# design.net
KiCad netlist of a schematic drawn in EasyEDA Pro
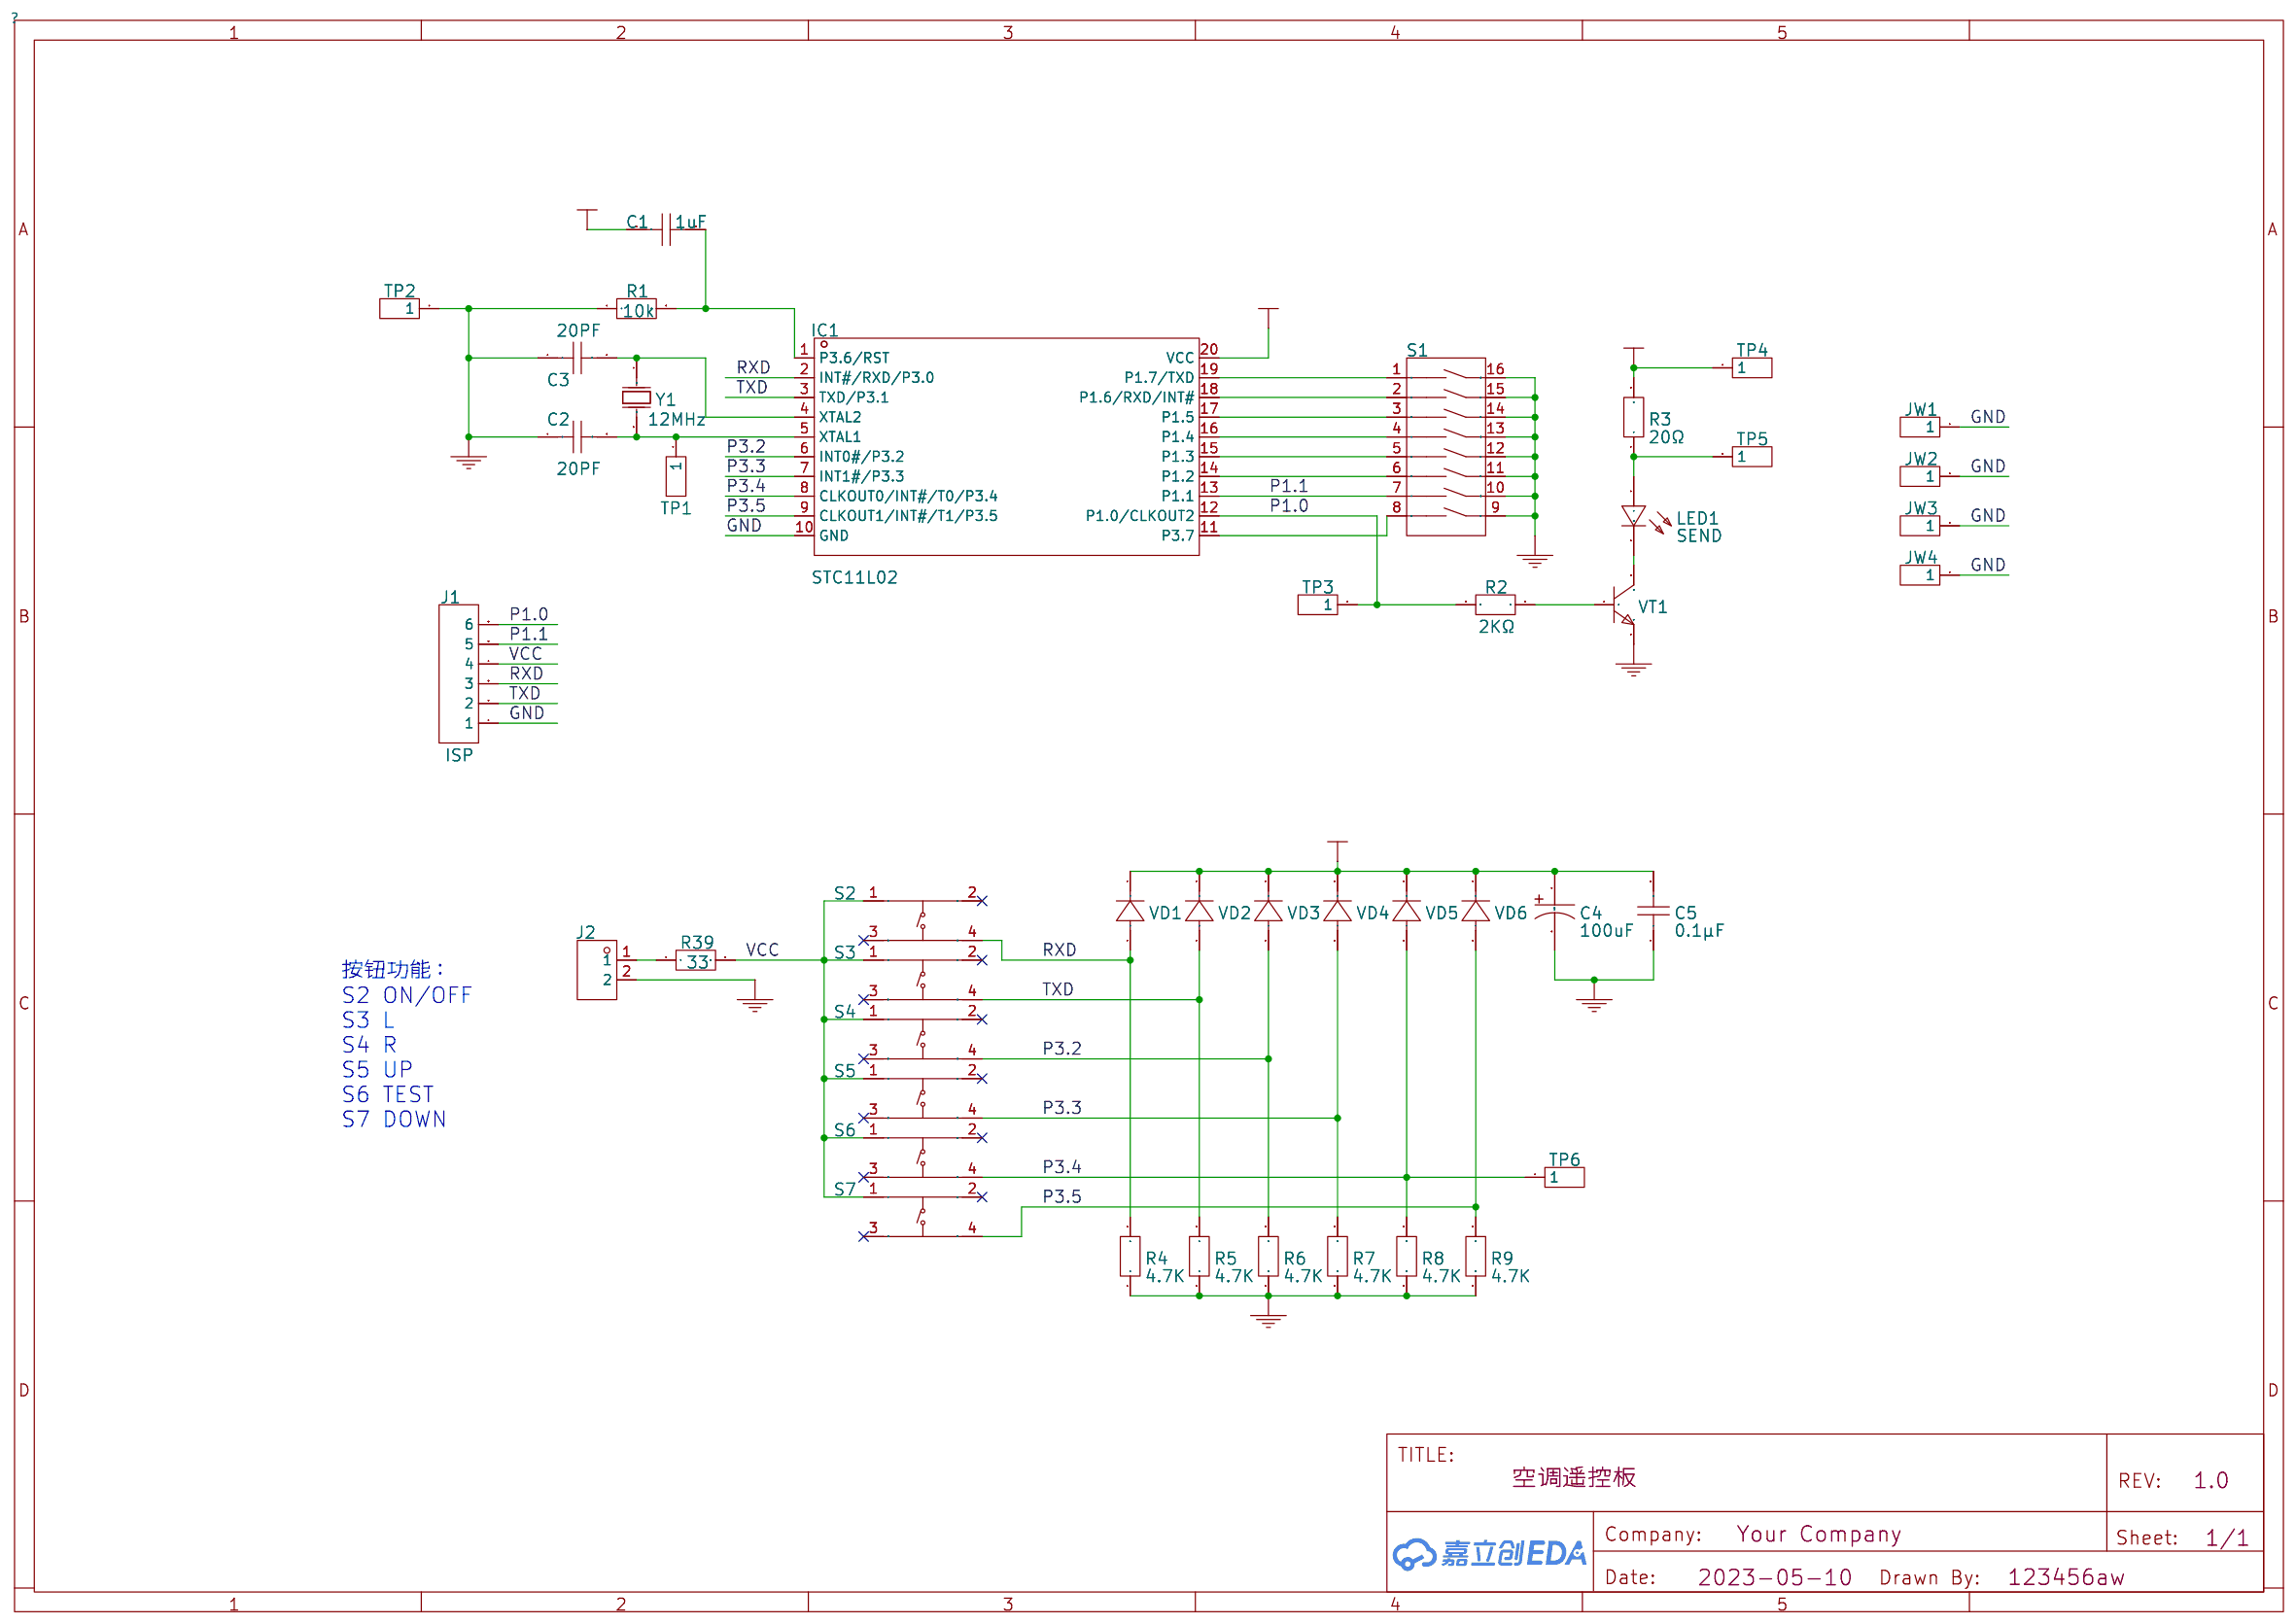
[diagram p0: schematic sheet]

(export (version "E")
  (design (tool "Eeschema 10.0.6"))
  (components
    (comp (ref "C1") (value "1uF") (footprint "easyedapro:C0805") (libsource (lib "easyedapro") (part "1uF")))
    (comp (ref "C2")
      (value "20PF")
      (footprint "easyedapro:C0805")
      (libsource (lib "easyedapro") (part "20PF"))
    )
    (comp (ref "C3")
      (value "20PF")
      (footprint "easyedapro:C0805")
      (libsource (lib "easyedapro") (part "20PF"))
    )
    (comp (ref "C4")
      (value "100uF")
      (footprint "easyedapro:CASE-C_6032")
      (fields (field (name "Manufacturer Part") "F931C107KCC") (field (name "Manufacturer") "Kyocera AVX"))
      (libsource (lib "easyedapro") (part "100uF"))
    )
    (comp (ref "C5")
      (value "0.1μF")
      (footprint "easyedapro:C0805")
      (libsource (lib "easyedapro") (part "0.1μF"))
    )
    (comp (ref "IC1")
      (value "STC11L02")
      (footprint "easyedapro:SOIC-20_L13.0-W7.6-P1.27-LS10.3-BL")
      (fields (field (name "Manufacturer") "STC(宏晶)"))
      (libsource (lib "easyedapro") (part "STC11L02"))
    )
    (comp (ref "J1")
      (value "ISP")
      (footprint "easyedapro:HDR-F-2.54_1X6")
      (libsource (lib "easyedapro") (part "ISP"))
    )
    (comp (ref "J2")
      (value "+3V GND")
      (footprint "easyedapro:CONN-TH_HX20020-2A")
      (fields (field (name "Manufacturer Part") "HX20020-2A") (field (name "Manufacturer") "HX(红星)"))
      (libsource (lib "easyedapro") (part "+3V GND"))
    )
    (comp (ref "JW1")
      (value "HDR-M-2.54_1x1")
      (footprint "easyedapro:焊盘M3")
      (libsource (lib "easyedapro") (part "HDR-M-2.54_1x1"))
    )
    (comp (ref "JW2")
      (value "HDR-M-2.54_1x1")
      (footprint "easyedapro:焊盘M3")
      (libsource (lib "easyedapro") (part "HDR-M-2.54_1x1"))
    )
    (comp (ref "JW3")
      (value "HDR-M-2.54_1x1")
      (footprint "easyedapro:焊盘M3")
      (libsource (lib "easyedapro") (part "HDR-M-2.54_1x1"))
    )
    (comp (ref "JW4")
      (value "HDR-M-2.54_1x1")
      (footprint "easyedapro:焊盘M3")
      (libsource (lib "easyedapro") (part "HDR-M-2.54_1x1"))
    )
    (comp (ref "LED1")
      (value "SEND")
      (footprint "easyedapro:LED-TH_BD3.9-P2.54-FD")
      (fields (field (name "Manufacturer Part") "IR204C-A-L") (field (name "Manufacturer") "EVERLIGHT(亿光)"))
      (libsource (lib "") (part "SEND_1"))
    )
    (comp (ref "R1") (value "10k") (footprint "easyedapro:R0805") (libsource (lib "easyedapro") (part "10k")))
    (comp (ref "R2") (value "2KΩ") (footprint "easyedapro:R0805") (libsource (lib "easyedapro") (part "2KΩ")))
    (comp (ref "R3")
      (value "20Ω")
      (footprint "easyedapro:RES-TH_BD3.5-L9.0-P13.00-D0.5")
      (fields (field (name "Manufacturer Part") "KNP1/2W-51Ω±5%-XT52") (field (name "Manufacturer") "VO(翔胜)"))
      (libsource (lib "easyedapro") (part "20Ω"))
    )
    (comp (ref "R4")
      (value "4.7K")
      (footprint "easyedapro:R0805")
      (libsource (lib "easyedapro") (part "4.7K"))
    )
    (comp (ref "R5")
      (value "4.7K")
      (footprint "easyedapro:R0805")
      (libsource (lib "easyedapro") (part "4.7K"))
    )
    (comp (ref "R6")
      (value "4.7K")
      (footprint "easyedapro:R0805")
      (libsource (lib "easyedapro") (part "4.7K"))
    )
    (comp (ref "R7")
      (value "4.7K")
      (footprint "easyedapro:R0805")
      (libsource (lib "easyedapro") (part "4.7K"))
    )
    (comp (ref "R8")
      (value "4.7K")
      (footprint "easyedapro:R0805")
      (libsource (lib "easyedapro") (part "4.7K"))
    )
    (comp (ref "R9")
      (value "4.7K")
      (footprint "easyedapro:R0805")
      (libsource (lib "easyedapro") (part "4.7K"))
    )
    (comp (ref "R39") (value "33") (footprint "easyedapro:R0805") (libsource (lib "easyedapro") (part "33")))
    (comp (ref "S1")
      (value "ADD")
      (footprint "easyedapro:SW-TH_16P-L21.9-W9.9-P2.54-LS7.8")
      (fields (field (name "Manufacturer Part") "2.54插件8位拨码开关"))
      (libsource (lib "easyedapro") (part "ADD"))
    )
    (comp (ref "S2")
      (value "ON/OFF")
      (footprint "easyedapro:SW-TH_4P-L6.0-W6.0-P4.50-LS6.5")
      (fields (field (name "Manufacturer Part") "TS665CJ") (field (name "Manufacturer") "SHOU HAN(首韩)"))
      (libsource (lib "easyedapro") (part "ON/OFF"))
    )
    (comp (ref "S3")
      (value "L")
      (footprint "easyedapro:SW-TH_4P-L6.0-W6.0-P4.50-LS6.5")
      (fields (field (name "Manufacturer Part") "TS665CJ") (field (name "Manufacturer") "SHOU HAN(首韩)"))
      (libsource (lib "easyedapro") (part "L"))
    )
    (comp (ref "S4")
      (value "R")
      (footprint "easyedapro:SW-TH_4P-L6.0-W6.0-P4.50-LS6.5")
      (fields (field (name "Manufacturer Part") "TS665CJ") (field (name "Manufacturer") "SHOU HAN(首韩)"))
      (libsource (lib "easyedapro") (part "R"))
    )
    (comp (ref "S5")
      (value "UP")
      (footprint "easyedapro:SW-TH_4P-L6.0-W6.0-P4.50-LS6.5")
      (fields (field (name "Manufacturer Part") "TS665CJ") (field (name "Manufacturer") "SHOU HAN(首韩)"))
      (libsource (lib "easyedapro") (part "UP"))
    )
    (comp (ref "S6")
      (value "TEST")
      (footprint "easyedapro:SW-TH_4P-L6.0-W6.0-P4.50-LS6.5")
      (fields (field (name "Manufacturer Part") "TS665CJ") (field (name "Manufacturer") "SHOU HAN(首韩)"))
      (libsource (lib "") (part "TEST_1"))
    )
    (comp (ref "S7")
      (value "DOWM")
      (footprint "easyedapro:SW-TH_4P-L6.0-W6.0-P4.50-LS6.5")
      (fields (field (name "Manufacturer Part") "TS665CJ") (field (name "Manufacturer") "SHOU HAN(首韩)"))
      (libsource (lib "easyedapro") (part "DOWM"))
    )
    (comp (ref "TP1")
      (value "XTAL")
      (footprint "easyedapro:HDR-M-2.54_1X1")
      (libsource (lib "easyedapro") (part "XTAL"))
    )
    (comp (ref "TP2")
      (value "GND")
      (footprint "easyedapro:HDR-M-2.54_1X1")
      (libsource (lib "") (part "GND_1"))
    )
    (comp (ref "TP3")
      (value "SEND")
      (footprint "easyedapro:HDR-M-2.54_1X1")
      (libsource (lib "easyedapro") (part "SEND"))
    )
    (comp (ref "TP4")
      (value "VCC")
      (footprint "easyedapro:HDR-M-2.54_1X1")
      (libsource (lib "") (part "VCC_1"))
    )
    (comp (ref "TP5")
      (value "RS")
      (footprint "easyedapro:HDR-M-2.54_1X1")
      (libsource (lib "easyedapro") (part "RS"))
    )
    (comp (ref "TP6")
      (value "TEST")
      (footprint "easyedapro:HDR-M-2.54_1X1")
      (libsource (lib "easyedapro") (part "TEST"))
    )
    (comp (ref "VD1")
      (value "1N5819_C9900008009")
      (footprint "easyedapro:SMA_L4.3-W2.6-LS5.1-RD")
      (fields (field (name "Manufacturer Part") "1N5819"))
      (libsource (lib "easyedapro") (part "1N5819_C9900008009"))
    )
    (comp (ref "VD2")
      (value "1N5819_C9900008009")
      (footprint "easyedapro:SMA_L4.3-W2.6-LS5.1-RD")
      (fields (field (name "Manufacturer Part") "1N5819"))
      (libsource (lib "easyedapro") (part "1N5819_C9900008009"))
    )
    (comp (ref "VD3")
      (value "1N5819_C9900008009")
      (footprint "easyedapro:SMA_L4.3-W2.6-LS5.1-RD")
      (fields (field (name "Manufacturer Part") "1N5819"))
      (libsource (lib "easyedapro") (part "1N5819_C9900008009"))
    )
    (comp (ref "VD4")
      (value "1N5819_C9900008009")
      (footprint "easyedapro:SMA_L4.3-W2.6-LS5.1-RD")
      (fields (field (name "Manufacturer Part") "1N5819"))
      (libsource (lib "easyedapro") (part "1N5819_C9900008009"))
    )
    (comp (ref "VD5")
      (value "1N5819_C9900008009")
      (footprint "easyedapro:SMA_L4.3-W2.6-LS5.1-RD")
      (fields (field (name "Manufacturer Part") "1N5819"))
      (libsource (lib "easyedapro") (part "1N5819_C9900008009"))
    )
    (comp (ref "VD6")
      (value "1N5819_C9900008009")
      (footprint "easyedapro:SMA_L4.3-W2.6-LS5.1-RD")
      (fields (field (name "Manufacturer Part") "1N5819"))
      (libsource (lib "easyedapro") (part "1N5819_C9900008009"))
    )
    (comp (ref "VT1")
      (value "S8050_C105433")
      (footprint "easyedapro:SOT-23-3_L2.9-W1.6-P1.90-LS2.8-BR")
      (fields (field (name "Manufacturer Part") "S8050") (field (name "Manufacturer") "CJ(江苏长电/长晶)"))
      (libsource (lib "easyedapro") (part "S8050_C105433"))
    )
    (comp (ref "Y1")
      (value "12MHz")
      (footprint "easyedapro:HC-49US_L11.5-W4.5-P4.88")
      (fields (field (name "Manufacturer Part") "X49SD12MSD2SC") (field (name "Manufacturer") "YXC(扬兴晶振)"))
      (libsource (lib "easyedapro") (part "12MHz"))
    )
  )
  (nets
    (net (code "1") (name "/P1.0") (class "Default")
      (node (ref "IC1") (pin "12") (pinfunction "P1.0/CLKOUT2_12") (pintype "input"))
      (node (ref "J1") (pin "6") (pinfunction "6_6") (pintype "input"))
      (node (ref "R2") (pin "2") (pinfunction "2_2") (pintype "input"))
      (node (ref "TP3") (pin "1") (pinfunction "1_1") (pintype "input"))
    )
    (net (code "2") (name "/P1.1") (class "Default")
      (node (ref "IC1") (pin "13") (pinfunction "P1.1_13") (pintype "input"))
      (node (ref "J1") (pin "5") (pinfunction "5_5") (pintype "input"))
      (node (ref "S1") (pin "7") (pinfunction "7_7") (pintype "input"))
    )
    (net (code "3") (name "/P3.2") (class "Default")
      (node (ref "IC1") (pin "6") (pinfunction "INT0#/P3.2_6") (pintype "input"))
      (node (ref "R6") (pin "2") (pinfunction "2_2") (pintype "input"))
      (node (ref "S4") (pin "4") (pinfunction "D_4") (pintype "input"))
      (node (ref "VD3") (pin "2") (pinfunction "A_2") (pintype "input"))
    )
    (net (code "4") (name "/P3.3") (class "Default")
      (node (ref "IC1") (pin "7") (pinfunction "INT1#/P3.3_7") (pintype "input"))
      (node (ref "R7") (pin "2") (pinfunction "2_2") (pintype "input"))
      (node (ref "S5") (pin "4") (pinfunction "D_4") (pintype "input"))
      (node (ref "VD4") (pin "2") (pinfunction "A_2") (pintype "input"))
    )
    (net (code "5") (name "/P3.4") (class "Default")
      (node (ref "IC1") (pin "8") (pinfunction "CLKOUT0/INT#/T0/P3.4_8") (pintype "input"))
      (node (ref "R8") (pin "2") (pinfunction "2_2") (pintype "input"))
      (node (ref "S6") (pin "4") (pinfunction "D_4") (pintype "input"))
      (node (ref "TP6") (pin "1") (pinfunction "1_1") (pintype "input"))
      (node (ref "VD5") (pin "2") (pinfunction "A_2") (pintype "input"))
    )
    (net (code "6") (name "/P3.5") (class "Default")
      (node (ref "IC1") (pin "9") (pinfunction "CLKOUT1/INT#/T1/P3.5_9") (pintype "input"))
      (node (ref "R9") (pin "2") (pinfunction "2_2") (pintype "input"))
      (node (ref "S7") (pin "4") (pinfunction "D_4") (pintype "input"))
      (node (ref "VD6") (pin "2") (pinfunction "A_2") (pintype "input"))
    )
    (net (code "7") (name "/RXD") (class "Default")
      (node (ref "IC1") (pin "2") (pinfunction "INT#/RXD/P3.0_2") (pintype "input"))
      (node (ref "J1") (pin "3") (pinfunction "3_3") (pintype "input"))
      (node (ref "R4") (pin "2") (pinfunction "2_2") (pintype "input"))
      (node (ref "S2") (pin "4") (pinfunction "D_4") (pintype "input"))
      (node (ref "VD1") (pin "2") (pinfunction "A_2") (pintype "input"))
    )
    (net (code "8") (name "/TXD") (class "Default")
      (node (ref "IC1") (pin "3") (pinfunction "TXD/P3.1_3") (pintype "input"))
      (node (ref "J1") (pin "2") (pinfunction "2_2") (pintype "input"))
      (node (ref "R5") (pin "2") (pinfunction "2_2") (pintype "input"))
      (node (ref "S3") (pin "4") (pinfunction "D_4") (pintype "input"))
      (node (ref "VD2") (pin "2") (pinfunction "A_2") (pintype "input"))
    )
    (net (code "9") (name "GND") (class "Default")
      (node (ref "C2") (pin "1") (pinfunction "1_1") (pintype "input"))
      (node (ref "C3") (pin "1") (pinfunction "1_1") (pintype "input"))
      (node (ref "C4") (pin "2") (pinfunction "2_2") (pintype "input"))
      (node (ref "C5") (pin "1") (pinfunction "1_1") (pintype "input"))
      (node (ref "IC1") (pin "10") (pinfunction "GND_10") (pintype "input"))
      (node (ref "J1") (pin "1") (pinfunction "1_1") (pintype "input"))
      (node (ref "J2") (pin "2") (pinfunction "2_2") (pintype "input"))
      (node (ref "JW1") (pin "1") (pinfunction "1_1") (pintype "input"))
      (node (ref "JW2") (pin "1") (pinfunction "1_1") (pintype "input"))
      (node (ref "JW3") (pin "1") (pinfunction "1_1") (pintype "input"))
      (node (ref "JW4") (pin "1") (pinfunction "1_1") (pintype "input"))
      (node (ref "R1") (pin "1") (pinfunction "1_1") (pintype "input"))
      (node (ref "R4") (pin "1") (pinfunction "1_1") (pintype "input"))
      (node (ref "R5") (pin "1") (pinfunction "1_1") (pintype "input"))
      (node (ref "R6") (pin "1") (pinfunction "1_1") (pintype "input"))
      (node (ref "R7") (pin "1") (pinfunction "1_1") (pintype "input"))
      (node (ref "R8") (pin "1") (pinfunction "1_1") (pintype "input"))
      (node (ref "R9") (pin "1") (pinfunction "1_1") (pintype "input"))
      (node (ref "S1") (pin "10") (pinfunction "10_10") (pintype "input"))
      (node (ref "S1") (pin "11") (pinfunction "11_11") (pintype "input"))
      (node (ref "S1") (pin "12") (pinfunction "12_12") (pintype "input"))
      (node (ref "S1") (pin "13") (pinfunction "13_13") (pintype "input"))
      (node (ref "S1") (pin "14") (pinfunction "14_14") (pintype "input"))
      (node (ref "S1") (pin "15") (pinfunction "15_15") (pintype "input"))
      (node (ref "S1") (pin "16") (pinfunction "16_16") (pintype "input"))
      (node (ref "S1") (pin "9") (pinfunction "9_9") (pintype "input"))
      (node (ref "TP2") (pin "1") (pinfunction "1_1") (pintype "input"))
      (node (ref "VT1") (pin "2") (pinfunction "2_2") (pintype "input"))
    )
    (net (code "10") (name "Net-(IC1-P1.2)") (class "Default")
      (node (ref "IC1") (pin "14") (pinfunction "P1.2_14") (pintype "input"))
      (node (ref "S1") (pin "6") (pinfunction "6_6") (pintype "input"))
    )
    (net (code "11") (name "Net-(IC1-P1.3)") (class "Default")
      (node (ref "IC1") (pin "15") (pinfunction "P1.3_15") (pintype "input"))
      (node (ref "S1") (pin "5") (pinfunction "5_5") (pintype "input"))
    )
    (net (code "12") (name "Net-(IC1-P1.4)") (class "Default")
      (node (ref "IC1") (pin "16") (pinfunction "P1.4_16") (pintype "input"))
      (node (ref "S1") (pin "4") (pinfunction "4_4") (pintype "input"))
    )
    (net (code "13") (name "Net-(IC1-P1.5)") (class "Default")
      (node (ref "IC1") (pin "17") (pinfunction "P1.5_17") (pintype "input"))
      (node (ref "S1") (pin "3") (pinfunction "3_3") (pintype "input"))
    )
    (net (code "14") (name "Net-(IC1-P1.6{slash}RXD{slash}INT#)") (class "Default")
      (node (ref "IC1") (pin "18") (pinfunction "P1.6/RXD/INT#_18") (pintype "input"))
      (node (ref "S1") (pin "2") (pinfunction "2_2") (pintype "input"))
    )
    (net (code "15") (name "Net-(IC1-P1.7{slash}TXD)") (class "Default")
      (node (ref "IC1") (pin "19") (pinfunction "P1.7/TXD_19") (pintype "input"))
      (node (ref "S1") (pin "1") (pinfunction "1_1") (pintype "input"))
    )
    (net (code "16") (name "Net-(IC1-P3.6{slash}RST)") (class "Default")
      (node (ref "C1") (pin "2") (pinfunction "2_2") (pintype "input"))
      (node (ref "IC1") (pin "1") (pinfunction "P3.6/RST_1") (pintype "input"))
      (node (ref "R1") (pin "2") (pinfunction "2_2") (pintype "input"))
    )
    (net (code "17") (name "Net-(IC1-P3.7)") (class "Default")
      (node (ref "IC1") (pin "11") (pinfunction "P3.7_11") (pintype "input"))
      (node (ref "S1") (pin "8") (pinfunction "8_8") (pintype "input"))
    )
    (net (code "18") (name "Net-(IC1-XTAL1)") (class "Default")
      (node (ref "C2") (pin "2") (pinfunction "2_2") (pintype "input"))
      (node (ref "IC1") (pin "5") (pinfunction "XTAL1_5") (pintype "input"))
      (node (ref "TP1") (pin "1") (pinfunction "1_1") (pintype "input"))
      (node (ref "Y1") (pin "2") (pinfunction "OSC2_2") (pintype "input"))
    )
    (net (code "19") (name "Net-(IC1-XTAL2)") (class "Default")
      (node (ref "C3") (pin "2") (pinfunction "2_2") (pintype "input"))
      (node (ref "IC1") (pin "4") (pinfunction "XTAL2_4") (pintype "input"))
      (node (ref "Y1") (pin "1") (pinfunction "OSC1_1") (pintype "input"))
    )
    (net (code "20") (name "Net-(J2-Pad1)") (class "Default")
      (node (ref "J2") (pin "1") (pinfunction "1_1") (pintype "input"))
      (node (ref "R39") (pin "1") (pinfunction "1_1") (pintype "input"))
    )
    (net (code "21") (name "Net-(LED1-A)") (class "Default")
      (node (ref "LED1") (pin "1") (pinfunction "A_1") (pintype "input"))
      (node (ref "R3") (pin "1") (pinfunction "1_1") (pintype "input"))
      (node (ref "TP5") (pin "1") (pinfunction "1_1") (pintype "input"))
    )
    (net (code "22") (name "Net-(LED1-C)") (class "Default")
      (node (ref "LED1") (pin "2") (pinfunction "C_2") (pintype "input"))
      (node (ref "VT1") (pin "3") (pinfunction "3_3") (pintype "input"))
    )
    (net (code "23") (name "Net-(R2-Pad1)") (class "Default")
      (node (ref "R2") (pin "1") (pinfunction "1_1") (pintype "input"))
      (node (ref "VT1") (pin "1") (pinfunction "1_1") (pintype "input"))
    )
    (net (code "24") (name "VCC") (class "Default")
      (node (ref "C1") (pin "1") (pinfunction "1_1") (pintype "input"))
      (node (ref "C4") (pin "1") (pinfunction "1_1") (pintype "input"))
      (node (ref "C5") (pin "2") (pinfunction "2_2") (pintype "input"))
      (node (ref "IC1") (pin "20") (pinfunction "VCC_20") (pintype "input"))
      (node (ref "J1") (pin "4") (pinfunction "4_4") (pintype "input"))
      (node (ref "R3") (pin "2") (pinfunction "2_2") (pintype "input"))
      (node (ref "R39") (pin "2") (pinfunction "2_2") (pintype "input"))
      (node (ref "S2") (pin "1") (pinfunction "A_1") (pintype "input"))
      (node (ref "S3") (pin "1") (pinfunction "A_1") (pintype "input"))
      (node (ref "S4") (pin "1") (pinfunction "A_1") (pintype "input"))
      (node (ref "S5") (pin "1") (pinfunction "A_1") (pintype "input"))
      (node (ref "S6") (pin "1") (pinfunction "A_1") (pintype "input"))
      (node (ref "S7") (pin "1") (pinfunction "A_1") (pintype "input"))
      (node (ref "TP4") (pin "1") (pinfunction "1_1") (pintype "input"))
      (node (ref "VD1") (pin "1") (pinfunction "K_1") (pintype "input"))
      (node (ref "VD2") (pin "1") (pinfunction "K_1") (pintype "input"))
      (node (ref "VD3") (pin "1") (pinfunction "K_1") (pintype "input"))
      (node (ref "VD4") (pin "1") (pinfunction "K_1") (pintype "input"))
      (node (ref "VD5") (pin "1") (pinfunction "K_1") (pintype "input"))
      (node (ref "VD6") (pin "1") (pinfunction "K_1") (pintype "input"))
    )
    (net (code "25") (name "unconnected-(S2-B-Pad2)") (class "Default")
      (node (ref "S2") (pin "2") (pinfunction "B_2") (pintype "input+no_connect"))
    )
    (net (code "26") (name "unconnected-(S2-C-Pad3)") (class "Default")
      (node (ref "S2") (pin "3") (pinfunction "C_3") (pintype "input+no_connect"))
    )
    (net (code "27") (name "unconnected-(S3-B-Pad2)") (class "Default")
      (node (ref "S3") (pin "2") (pinfunction "B_2") (pintype "input+no_connect"))
    )
    (net (code "28") (name "unconnected-(S3-C-Pad3)") (class "Default")
      (node (ref "S3") (pin "3") (pinfunction "C_3") (pintype "input+no_connect"))
    )
    (net (code "29") (name "unconnected-(S4-B-Pad2)") (class "Default")
      (node (ref "S4") (pin "2") (pinfunction "B_2") (pintype "input+no_connect"))
    )
    (net (code "30") (name "unconnected-(S4-C-Pad3)") (class "Default")
      (node (ref "S4") (pin "3") (pinfunction "C_3") (pintype "input+no_connect"))
    )
    (net (code "31") (name "unconnected-(S5-B-Pad2)") (class "Default")
      (node (ref "S5") (pin "2") (pinfunction "B_2") (pintype "input+no_connect"))
    )
    (net (code "32") (name "unconnected-(S5-C-Pad3)") (class "Default")
      (node (ref "S5") (pin "3") (pinfunction "C_3") (pintype "input+no_connect"))
    )
    (net (code "33") (name "unconnected-(S6-B-Pad2)") (class "Default")
      (node (ref "S6") (pin "2") (pinfunction "B_2") (pintype "input+no_connect"))
    )
    (net (code "34") (name "unconnected-(S6-C-Pad3)") (class "Default")
      (node (ref "S6") (pin "3") (pinfunction "C_3") (pintype "input+no_connect"))
    )
    (net (code "35") (name "unconnected-(S7-B-Pad2)") (class "Default")
      (node (ref "S7") (pin "2") (pinfunction "B_2") (pintype "input+no_connect"))
    )
    (net (code "36") (name "unconnected-(S7-C-Pad3)") (class "Default")
      (node (ref "S7") (pin "3") (pinfunction "C_3") (pintype "input+no_connect"))
    )
  )
)
